# Pinduino-Nano-Sys11b.net
KiCad netlist of a schematic drawn in EAGLE
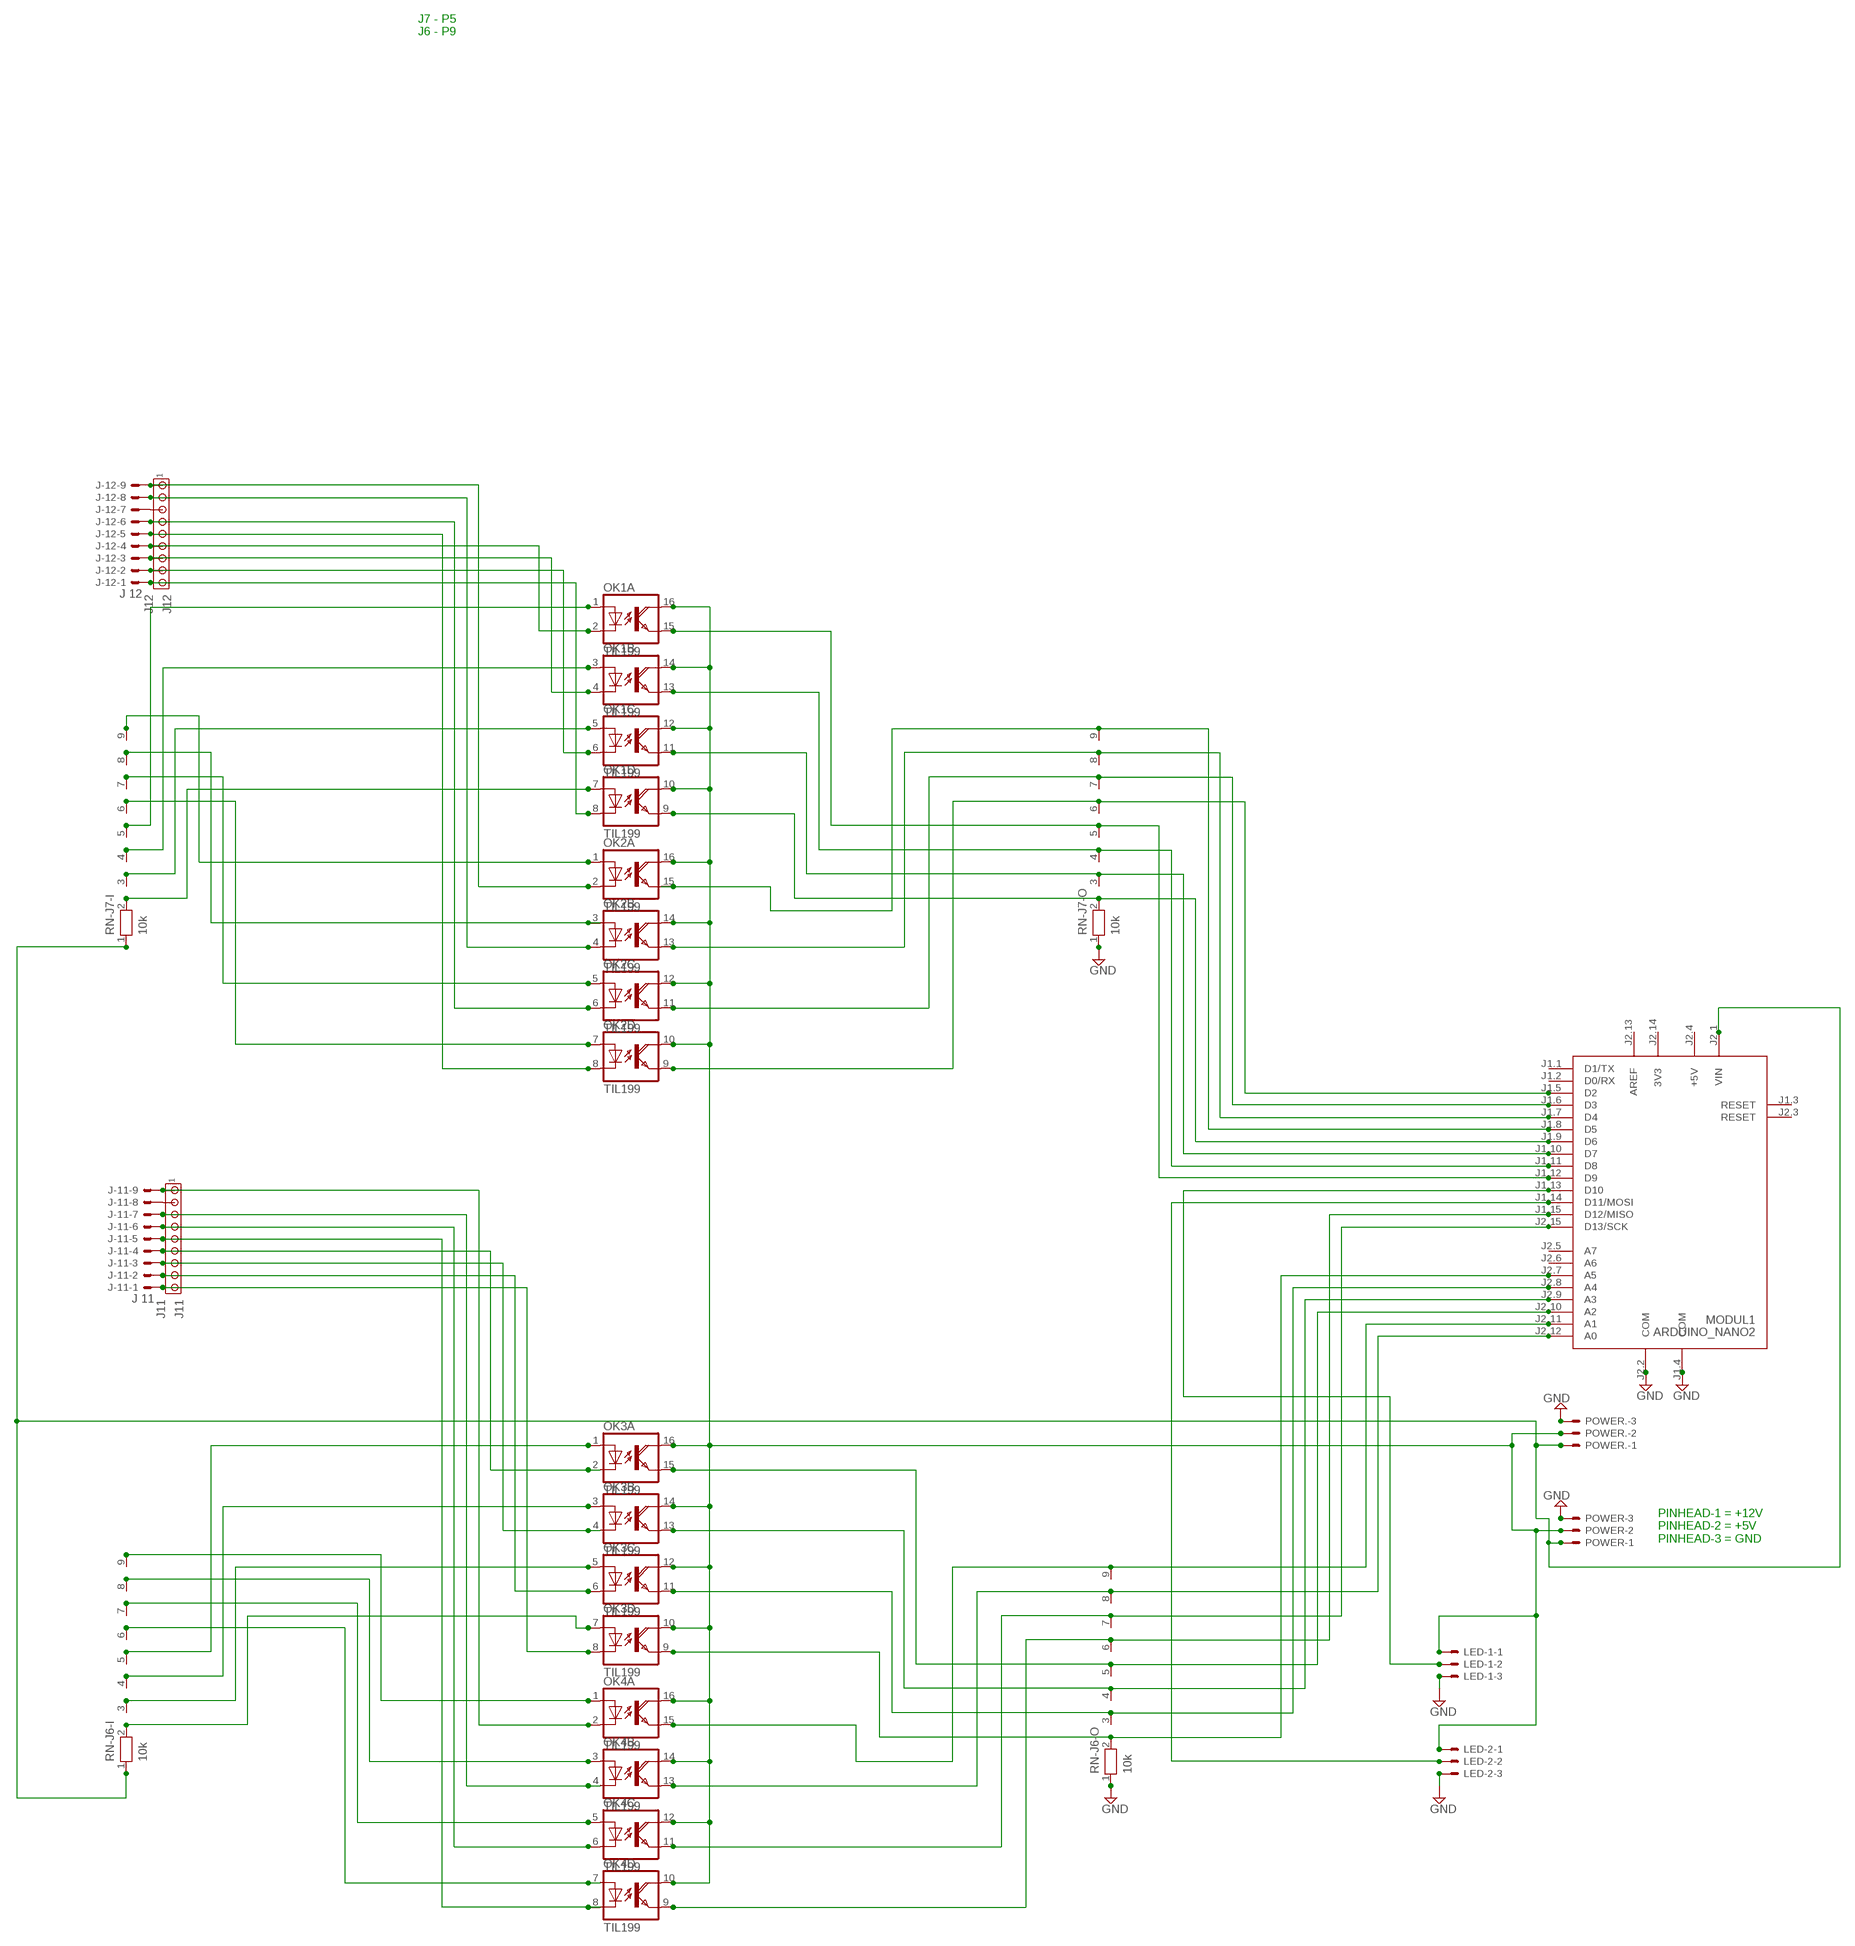
[diagram p0: schematic, sheet 1]

(export (version "E")
  (design (tool "Eeschema 10.0.6"))
  (components
    (comp (ref "J-11")
      (value "J 11")
      (footprint "eagle-import:KK-156-9")
      (libsource (lib "eagle-import") (part "KK-156-9"))
    )
    (comp (ref "J-12")
      (value "J 12")
      (footprint "eagle-import:KK-156-9")
      (libsource (lib "eagle-import") (part "KK-156-9"))
    )
    (comp (ref "J11")
      (value "J11")
      (footprint "eagle-import:1X9MTA")
      (libsource (lib "eagle-import") (part "MTA09-156"))
    )
    (comp (ref "J12")
      (value "J12")
      (footprint "eagle-import:1X9MTA")
      (libsource (lib "eagle-import") (part "MTA09-156"))
    )
    (comp (ref "LED-1")
      (value "22-23-2031")
      (footprint "eagle-import:22-23-2031")
      (fields (field (name "MF") "MOLEX"))
      (libsource (lib "eagle-import") (part "22-23-2031"))
    )
    (comp (ref "LED-2")
      (value "22-23-2031")
      (footprint "eagle-import:22-23-2031")
      (fields (field (name "MF") "MOLEX"))
      (libsource (lib "eagle-import") (part "22-23-2031"))
    )
    (comp (ref "MODUL1")
      (value "ARDUINO_NANO2")
      (footprint "eagle-import:ARDUINO_NANO2")
      (libsource (lib "eagle-import") (part "ARDUINO_NANO2"))
    )
    (comp (ref "OK1")
      (value "TIL199")
      (footprint "eagle-import:DIL16")
      (fields (field (name "MPN") "TIL 199"))
      (libsource (lib "eagle-import") (part "TIL199"))
    )
    (comp (ref "OK2")
      (value "TIL199")
      (footprint "eagle-import:DIL16")
      (fields (field (name "MPN") "TIL 199"))
      (libsource (lib "eagle-import") (part "TIL199"))
    )
    (comp (ref "OK3")
      (value "TIL199")
      (footprint "eagle-import:DIL16")
      (fields (field (name "MPN") "TIL 199"))
      (libsource (lib "eagle-import") (part "TIL199"))
    )
    (comp (ref "OK4")
      (value "TIL199")
      (footprint "eagle-import:DIL16")
      (fields (field (name "MPN") "TIL 199"))
      (libsource (lib "eagle-import") (part "TIL199"))
    )
    (comp (ref "POWER")
      (value "22-23-2031")
      (footprint "eagle-import:22-23-2031")
      (fields (field (name "MF") "MOLEX"))
      (libsource (lib "eagle-import") (part "22-23-2031"))
    )
    (comp (ref "POWER.")
      (value "22-23-2031")
      (footprint "eagle-import:22-23-2031")
      (fields (field (name "MF") "MOLEX"))
      (libsource (lib "eagle-import") (part "22-23-2031"))
    )
    (comp (ref "RN-J6-I")
      (value "10k")
      (footprint "eagle-import:RN-9")
      (libsource (lib "eagle-import") (part "RN08"))
    )
    (comp (ref "RN-J6-O")
      (value "10k")
      (footprint "eagle-import:RN-9")
      (libsource (lib "eagle-import") (part "RN08"))
    )
    (comp (ref "RN-J7-I")
      (value "10k")
      (footprint "eagle-import:RN-9")
      (libsource (lib "eagle-import") (part "RN08"))
    )
    (comp (ref "RN-J7-O")
      (value "10k")
      (footprint "eagle-import:RN-9")
      (libsource (lib "eagle-import") (part "RN08"))
    )
  )
  (nets
    (net (code "1") (name "/+5V") (class "Default")
      (node (ref "MODUL1") (pin "J2.4") (pinfunction "+5V_J2.4") (pintype "power_in"))
    )
    (net (code "2") (name "/3V3") (class "Default")
      (node (ref "MODUL1") (pin "J2.14") (pinfunction "3V3_J2.14") (pintype "power_in"))
    )
    (net (code "3") (name "/AREF") (class "Default")
      (node (ref "MODUL1") (pin "J2.13") (pinfunction "AREF_J2.13") (pintype "power_in"))
    )
    (net (code "4") (name "GND") (class "Default")
      (node (ref "LED-1") (pin "3") (pinfunction "S_3") (pintype "passive"))
      (node (ref "LED-2") (pin "3") (pinfunction "S_3") (pintype "passive"))
      (node (ref "MODUL1") (pin "J1.4") (pinfunction "COM_J1.4") (pintype "power_in"))
      (node (ref "MODUL1") (pin "J2.2") (pinfunction "COM_J2.2") (pintype "power_in"))
      (node (ref "POWER") (pin "3") (pinfunction "S_3") (pintype "passive"))
      (node (ref "POWER.") (pin "3") (pinfunction "S_3") (pintype "passive"))
      (node (ref "RN-J6-O") (pin "1") (pinfunction "1_1") (pintype "passive"))
      (node (ref "RN-J7-O") (pin "1") (pinfunction "1_1") (pintype "passive"))
    )
    (net (code "5") (name "Net-(J-11A-S)") (class "Default")
      (node (ref "J-11") (pin "1") (pinfunction "S_1") (pintype "passive"))
      (node (ref "J11") (pin "9") (pinfunction "9_9") (pintype "passive"))
      (node (ref "OK3") (pin "8") (pinfunction "C_8") (pintype "passive"))
    )
    (net (code "6") (name "Net-(J-11B-S)") (class "Default")
      (node (ref "J-11") (pin "2") (pinfunction "S_2") (pintype "passive"))
      (node (ref "J11") (pin "8") (pinfunction "8_8") (pintype "passive"))
      (node (ref "OK3") (pin "6") (pinfunction "C_6") (pintype "passive"))
    )
    (net (code "7") (name "Net-(J-11C-S)") (class "Default")
      (node (ref "J-11") (pin "3") (pinfunction "S_3") (pintype "passive"))
      (node (ref "J11") (pin "7") (pinfunction "7_7") (pintype "passive"))
      (node (ref "OK3") (pin "4") (pinfunction "C_4") (pintype "passive"))
    )
    (net (code "8") (name "Net-(J-11D-S)") (class "Default")
      (node (ref "J-11") (pin "4") (pinfunction "S_4") (pintype "passive"))
      (node (ref "J11") (pin "6") (pinfunction "6_6") (pintype "passive"))
      (node (ref "OK3") (pin "2") (pinfunction "C_2") (pintype "passive"))
    )
    (net (code "9") (name "Net-(J-11E-S)") (class "Default")
      (node (ref "J-11") (pin "5") (pinfunction "S_5") (pintype "passive"))
      (node (ref "J11") (pin "5") (pinfunction "5_5") (pintype "passive"))
      (node (ref "OK4") (pin "8") (pinfunction "C_8") (pintype "passive"))
    )
    (net (code "10") (name "Net-(J-11F-S)") (class "Default")
      (node (ref "J-11") (pin "6") (pinfunction "S_6") (pintype "passive"))
      (node (ref "J11") (pin "4") (pinfunction "4_4") (pintype "passive"))
      (node (ref "OK4") (pin "6") (pinfunction "C_6") (pintype "passive"))
    )
    (net (code "11") (name "Net-(J-11G-S)") (class "Default")
      (node (ref "J-11") (pin "7") (pinfunction "S_7") (pintype "passive"))
      (node (ref "J11") (pin "3") (pinfunction "3_3") (pintype "passive"))
      (node (ref "OK4") (pin "4") (pinfunction "C_4") (pintype "passive"))
    )
    (net (code "12") (name "Net-(J-11H-S)") (class "Default")
      (node (ref "J-11") (pin "8") (pinfunction "S_8") (pintype "passive"))
      (node (ref "J11") (pin "2") (pinfunction "2_2") (pintype "passive"))
    )
    (net (code "13") (name "Net-(J-11I-S)") (class "Default")
      (node (ref "J-11") (pin "9") (pinfunction "S_9") (pintype "passive"))
      (node (ref "J11") (pin "1") (pinfunction "1_1") (pintype "passive"))
      (node (ref "OK4") (pin "2") (pinfunction "C_2") (pintype "passive"))
    )
    (net (code "14") (name "Net-(J-12A-S)") (class "Default")
      (node (ref "J-12") (pin "1") (pinfunction "S_1") (pintype "passive"))
      (node (ref "J12") (pin "9") (pinfunction "9_9") (pintype "passive"))
      (node (ref "OK1") (pin "8") (pinfunction "C_8") (pintype "passive"))
    )
    (net (code "15") (name "Net-(J-12B-S)") (class "Default")
      (node (ref "J-12") (pin "2") (pinfunction "S_2") (pintype "passive"))
      (node (ref "J12") (pin "8") (pinfunction "8_8") (pintype "passive"))
      (node (ref "OK1") (pin "6") (pinfunction "C_6") (pintype "passive"))
    )
    (net (code "16") (name "Net-(J-12C-S)") (class "Default")
      (node (ref "J-12") (pin "3") (pinfunction "S_3") (pintype "passive"))
      (node (ref "J12") (pin "7") (pinfunction "7_7") (pintype "passive"))
      (node (ref "OK1") (pin "4") (pinfunction "C_4") (pintype "passive"))
    )
    (net (code "17") (name "Net-(J-12D-S)") (class "Default")
      (node (ref "J-12") (pin "4") (pinfunction "S_4") (pintype "passive"))
      (node (ref "J12") (pin "6") (pinfunction "6_6") (pintype "passive"))
      (node (ref "OK1") (pin "2") (pinfunction "C_2") (pintype "passive"))
    )
    (net (code "18") (name "Net-(J-12E-S)") (class "Default")
      (node (ref "J-12") (pin "5") (pinfunction "S_5") (pintype "passive"))
      (node (ref "J12") (pin "5") (pinfunction "5_5") (pintype "passive"))
      (node (ref "OK2") (pin "8") (pinfunction "C_8") (pintype "passive"))
    )
    (net (code "19") (name "Net-(J-12F-S)") (class "Default")
      (node (ref "J-12") (pin "6") (pinfunction "S_6") (pintype "passive"))
      (node (ref "J12") (pin "4") (pinfunction "4_4") (pintype "passive"))
      (node (ref "OK2") (pin "6") (pinfunction "C_6") (pintype "passive"))
    )
    (net (code "20") (name "Net-(J-12G-S)") (class "Default")
      (node (ref "J-12") (pin "7") (pinfunction "S_7") (pintype "passive"))
      (node (ref "J12") (pin "3") (pinfunction "3_3") (pintype "passive"))
    )
    (net (code "21") (name "Net-(J-12H-S)") (class "Default")
      (node (ref "J-12") (pin "8") (pinfunction "S_8") (pintype "passive"))
      (node (ref "J12") (pin "2") (pinfunction "2_2") (pintype "passive"))
      (node (ref "OK2") (pin "4") (pinfunction "C_4") (pintype "passive"))
    )
    (net (code "22") (name "Net-(J-12I-S)") (class "Default")
      (node (ref "J-12") (pin "9") (pinfunction "S_9") (pintype "passive"))
      (node (ref "J12") (pin "1") (pinfunction "1_1") (pintype "passive"))
      (node (ref "OK2") (pin "2") (pinfunction "C_2") (pintype "passive"))
    )
    (net (code "23") (name "Net-(LED-1A-S)") (class "Default")
      (node (ref "LED-1") (pin "1") (pinfunction "S_1") (pintype "passive"))
      (node (ref "LED-2") (pin "1") (pinfunction "S_1") (pintype "passive"))
      (node (ref "OK1") (pin "10") (pinfunction "COL_10") (pintype "passive"))
      (node (ref "OK1") (pin "12") (pinfunction "COL_12") (pintype "passive"))
      (node (ref "OK1") (pin "14") (pinfunction "COL_14") (pintype "passive"))
      (node (ref "OK1") (pin "16") (pinfunction "COL_16") (pintype "passive"))
      (node (ref "OK2") (pin "10") (pinfunction "COL_10") (pintype "passive"))
      (node (ref "OK2") (pin "12") (pinfunction "COL_12") (pintype "passive"))
      (node (ref "OK2") (pin "14") (pinfunction "COL_14") (pintype "passive"))
      (node (ref "OK2") (pin "16") (pinfunction "COL_16") (pintype "passive"))
      (node (ref "OK3") (pin "10") (pinfunction "COL_10") (pintype "passive"))
      (node (ref "OK3") (pin "12") (pinfunction "COL_12") (pintype "passive"))
      (node (ref "OK3") (pin "14") (pinfunction "COL_14") (pintype "passive"))
      (node (ref "OK3") (pin "16") (pinfunction "COL_16") (pintype "passive"))
      (node (ref "OK4") (pin "10") (pinfunction "COL_10") (pintype "passive"))
      (node (ref "OK4") (pin "12") (pinfunction "COL_12") (pintype "passive"))
      (node (ref "OK4") (pin "14") (pinfunction "COL_14") (pintype "passive"))
      (node (ref "OK4") (pin "16") (pinfunction "COL_16") (pintype "passive"))
      (node (ref "POWER") (pin "2") (pinfunction "S_2") (pintype "passive"))
      (node (ref "POWER.") (pin "2") (pinfunction "S_2") (pintype "passive"))
    )
    (net (code "24") (name "Net-(LED-1B-S)") (class "Default")
      (node (ref "LED-1") (pin "2") (pinfunction "S_2") (pintype "passive"))
      (node (ref "MODUL1") (pin "J1.13") (pinfunction "D10_J1.13") (pintype "bidirectional"))
    )
    (net (code "25") (name "Net-(LED-2B-S)") (class "Default")
      (node (ref "LED-2") (pin "2") (pinfunction "S_2") (pintype "passive"))
      (node (ref "MODUL1") (pin "J1.14") (pinfunction "D11/MOSI_J1.14") (pintype "bidirectional"))
    )
    (net (code "26") (name "Net-(MODUL1-A0)") (class "Default")
      (node (ref "MODUL1") (pin "J2.12") (pinfunction "A0_J2.12") (pintype "bidirectional"))
      (node (ref "OK4") (pin "13") (pinfunction "EMI_13") (pintype "passive"))
      (node (ref "RN-J6-O") (pin "8") (pinfunction "8_8") (pintype "passive"))
    )
    (net (code "27") (name "Net-(MODUL1-A1)") (class "Default")
      (node (ref "MODUL1") (pin "J2.11") (pinfunction "A1_J2.11") (pintype "bidirectional"))
      (node (ref "OK4") (pin "15") (pinfunction "EMI_15") (pintype "passive"))
      (node (ref "RN-J6-O") (pin "9") (pinfunction "9_9") (pintype "passive"))
    )
    (net (code "28") (name "Net-(MODUL1-A2)") (class "Default")
      (node (ref "MODUL1") (pin "J2.10") (pinfunction "A2_J2.10") (pintype "bidirectional"))
      (node (ref "OK3") (pin "15") (pinfunction "EMI_15") (pintype "passive"))
      (node (ref "RN-J6-O") (pin "5") (pinfunction "5_5") (pintype "passive"))
    )
    (net (code "29") (name "Net-(MODUL1-A3)") (class "Default")
      (node (ref "MODUL1") (pin "J2.9") (pinfunction "A3_J2.9") (pintype "bidirectional"))
      (node (ref "OK3") (pin "13") (pinfunction "EMI_13") (pintype "passive"))
      (node (ref "RN-J6-O") (pin "4") (pinfunction "4_4") (pintype "passive"))
    )
    (net (code "30") (name "Net-(MODUL1-A4)") (class "Default")
      (node (ref "MODUL1") (pin "J2.8") (pinfunction "A4_J2.8") (pintype "bidirectional"))
      (node (ref "OK3") (pin "11") (pinfunction "EMI_11") (pintype "passive"))
      (node (ref "RN-J6-O") (pin "3") (pinfunction "3_3") (pintype "passive"))
    )
    (net (code "31") (name "Net-(MODUL1-A5)") (class "Default")
      (node (ref "MODUL1") (pin "J2.7") (pinfunction "A5_J2.7") (pintype "bidirectional"))
      (node (ref "OK3") (pin "9") (pinfunction "EMI_9") (pintype "passive"))
      (node (ref "RN-J6-O") (pin "2") (pinfunction "2_2") (pintype "passive"))
    )
    (net (code "32") (name "Net-(MODUL1-D2)") (class "Default")
      (node (ref "MODUL1") (pin "J1.5") (pinfunction "D2_J1.5") (pintype "bidirectional"))
      (node (ref "OK2") (pin "9") (pinfunction "EMI_9") (pintype "passive"))
      (node (ref "RN-J7-O") (pin "6") (pinfunction "6_6") (pintype "passive"))
    )
    (net (code "33") (name "Net-(MODUL1-D3)") (class "Default")
      (node (ref "MODUL1") (pin "J1.6") (pinfunction "D3_J1.6") (pintype "bidirectional"))
      (node (ref "OK2") (pin "11") (pinfunction "EMI_11") (pintype "passive"))
      (node (ref "RN-J7-O") (pin "7") (pinfunction "7_7") (pintype "passive"))
    )
    (net (code "34") (name "Net-(MODUL1-D4)") (class "Default")
      (node (ref "MODUL1") (pin "J1.7") (pinfunction "D4_J1.7") (pintype "bidirectional"))
      (node (ref "OK2") (pin "13") (pinfunction "EMI_13") (pintype "passive"))
      (node (ref "RN-J7-O") (pin "8") (pinfunction "8_8") (pintype "passive"))
    )
    (net (code "35") (name "Net-(MODUL1-D5)") (class "Default")
      (node (ref "MODUL1") (pin "J1.8") (pinfunction "D5_J1.8") (pintype "bidirectional"))
      (node (ref "OK2") (pin "15") (pinfunction "EMI_15") (pintype "passive"))
      (node (ref "RN-J7-O") (pin "9") (pinfunction "9_9") (pintype "passive"))
    )
    (net (code "36") (name "Net-(MODUL1-D6)") (class "Default")
      (node (ref "MODUL1") (pin "J1.9") (pinfunction "D6_J1.9") (pintype "bidirectional"))
      (node (ref "OK1") (pin "9") (pinfunction "EMI_9") (pintype "passive"))
      (node (ref "RN-J7-O") (pin "2") (pinfunction "2_2") (pintype "passive"))
    )
    (net (code "37") (name "Net-(MODUL1-D7)") (class "Default")
      (node (ref "MODUL1") (pin "J1.10") (pinfunction "D7_J1.10") (pintype "bidirectional"))
      (node (ref "OK1") (pin "11") (pinfunction "EMI_11") (pintype "passive"))
      (node (ref "RN-J7-O") (pin "3") (pinfunction "3_3") (pintype "passive"))
    )
    (net (code "38") (name "Net-(MODUL1-D8)") (class "Default")
      (node (ref "MODUL1") (pin "J1.11") (pinfunction "D8_J1.11") (pintype "bidirectional"))
      (node (ref "OK1") (pin "13") (pinfunction "EMI_13") (pintype "passive"))
      (node (ref "RN-J7-O") (pin "4") (pinfunction "4_4") (pintype "passive"))
    )
    (net (code "39") (name "Net-(MODUL1-D9)") (class "Default")
      (node (ref "MODUL1") (pin "J1.12") (pinfunction "D9_J1.12") (pintype "bidirectional"))
      (node (ref "OK1") (pin "15") (pinfunction "EMI_15") (pintype "passive"))
      (node (ref "RN-J7-O") (pin "5") (pinfunction "5_5") (pintype "passive"))
    )
    (net (code "40") (name "Net-(MODUL1-D12{slash}MISO)") (class "Default")
      (node (ref "MODUL1") (pin "J1.15") (pinfunction "D12/MISO_J1.15") (pintype "bidirectional"))
      (node (ref "OK4") (pin "9") (pinfunction "EMI_9") (pintype "passive"))
      (node (ref "RN-J6-O") (pin "6") (pinfunction "6_6") (pintype "passive"))
    )
    (net (code "41") (name "Net-(MODUL1-D13{slash}SCK)") (class "Default")
      (node (ref "MODUL1") (pin "J2.15") (pinfunction "D13/SCK_J2.15") (pintype "bidirectional"))
      (node (ref "OK4") (pin "11") (pinfunction "EMI_11") (pintype "passive"))
      (node (ref "RN-J6-O") (pin "7") (pinfunction "7_7") (pintype "passive"))
    )
    (net (code "42") (name "Net-(MODUL1-VIN)") (class "Default")
      (node (ref "MODUL1") (pin "J2.1") (pinfunction "VIN_J2.1") (pintype "power_in"))
      (node (ref "POWER") (pin "1") (pinfunction "S_1") (pintype "passive"))
      (node (ref "POWER.") (pin "1") (pinfunction "S_1") (pintype "passive"))
      (node (ref "RN-J6-I") (pin "1") (pinfunction "1_1") (pintype "passive"))
      (node (ref "RN-J7-I") (pin "1") (pinfunction "1_1") (pintype "passive"))
    )
    (net (code "43") (name "Net-(OK1A-A)") (class "Default")
      (node (ref "OK1") (pin "1") (pinfunction "A_1") (pintype "passive"))
      (node (ref "RN-J7-I") (pin "5") (pinfunction "5_5") (pintype "passive"))
    )
    (net (code "44") (name "Net-(OK1B-A)") (class "Default")
      (node (ref "OK1") (pin "3") (pinfunction "A_3") (pintype "passive"))
      (node (ref "RN-J7-I") (pin "4") (pinfunction "4_4") (pintype "passive"))
    )
    (net (code "45") (name "Net-(OK1C-A)") (class "Default")
      (node (ref "OK1") (pin "5") (pinfunction "A_5") (pintype "passive"))
      (node (ref "RN-J7-I") (pin "3") (pinfunction "3_3") (pintype "passive"))
    )
    (net (code "46") (name "Net-(OK1D-A)") (class "Default")
      (node (ref "OK1") (pin "7") (pinfunction "A_7") (pintype "passive"))
      (node (ref "RN-J7-I") (pin "2") (pinfunction "2_2") (pintype "passive"))
    )
    (net (code "47") (name "Net-(OK2A-A)") (class "Default")
      (node (ref "OK2") (pin "1") (pinfunction "A_1") (pintype "passive"))
      (node (ref "RN-J7-I") (pin "9") (pinfunction "9_9") (pintype "passive"))
    )
    (net (code "48") (name "Net-(OK2B-A)") (class "Default")
      (node (ref "OK2") (pin "3") (pinfunction "A_3") (pintype "passive"))
      (node (ref "RN-J7-I") (pin "8") (pinfunction "8_8") (pintype "passive"))
    )
    (net (code "49") (name "Net-(OK2C-A)") (class "Default")
      (node (ref "OK2") (pin "5") (pinfunction "A_5") (pintype "passive"))
      (node (ref "RN-J7-I") (pin "7") (pinfunction "7_7") (pintype "passive"))
    )
    (net (code "50") (name "Net-(OK2D-A)") (class "Default")
      (node (ref "OK2") (pin "7") (pinfunction "A_7") (pintype "passive"))
      (node (ref "RN-J7-I") (pin "6") (pinfunction "6_6") (pintype "passive"))
    )
    (net (code "51") (name "Net-(OK3A-A)") (class "Default")
      (node (ref "OK3") (pin "1") (pinfunction "A_1") (pintype "passive"))
      (node (ref "RN-J6-I") (pin "5") (pinfunction "5_5") (pintype "passive"))
    )
    (net (code "52") (name "Net-(OK3B-A)") (class "Default")
      (node (ref "OK3") (pin "3") (pinfunction "A_3") (pintype "passive"))
      (node (ref "RN-J6-I") (pin "4") (pinfunction "4_4") (pintype "passive"))
    )
    (net (code "53") (name "Net-(OK3C-A)") (class "Default")
      (node (ref "OK3") (pin "5") (pinfunction "A_5") (pintype "passive"))
      (node (ref "RN-J6-I") (pin "3") (pinfunction "3_3") (pintype "passive"))
    )
    (net (code "54") (name "Net-(OK3D-A)") (class "Default")
      (node (ref "OK3") (pin "7") (pinfunction "A_7") (pintype "passive"))
      (node (ref "RN-J6-I") (pin "2") (pinfunction "2_2") (pintype "passive"))
    )
    (net (code "55") (name "Net-(OK4A-A)") (class "Default")
      (node (ref "OK4") (pin "1") (pinfunction "A_1") (pintype "passive"))
      (node (ref "RN-J6-I") (pin "9") (pinfunction "9_9") (pintype "passive"))
    )
    (net (code "56") (name "Net-(OK4B-A)") (class "Default")
      (node (ref "OK4") (pin "3") (pinfunction "A_3") (pintype "passive"))
      (node (ref "RN-J6-I") (pin "8") (pinfunction "8_8") (pintype "passive"))
    )
    (net (code "57") (name "Net-(OK4C-A)") (class "Default")
      (node (ref "OK4") (pin "5") (pinfunction "A_5") (pintype "passive"))
      (node (ref "RN-J6-I") (pin "7") (pinfunction "7_7") (pintype "passive"))
    )
    (net (code "58") (name "Net-(OK4D-A)") (class "Default")
      (node (ref "OK4") (pin "7") (pinfunction "A_7") (pintype "passive"))
      (node (ref "RN-J6-I") (pin "6") (pinfunction "6_6") (pintype "passive"))
    )
    (net (code "59") (name "unconnected-(MODUL1-A6-PadJ2.6)") (class "Default")
      (node (ref "MODUL1") (pin "J2.6") (pinfunction "A6_J2.6") (pintype "bidirectional"))
    )
    (net (code "60") (name "unconnected-(MODUL1-A7-PadJ2.5)") (class "Default")
      (node (ref "MODUL1") (pin "J2.5") (pinfunction "A7_J2.5") (pintype "bidirectional"))
    )
    (net (code "61") (name "unconnected-(MODUL1-D0{slash}RX-PadJ1.2)") (class "Default")
      (node (ref "MODUL1") (pin "J1.2") (pinfunction "D0/RX_J1.2") (pintype "bidirectional"))
    )
    (net (code "62") (name "unconnected-(MODUL1-D1{slash}TX-PadJ1.1)") (class "Default")
      (node (ref "MODUL1") (pin "J1.1") (pinfunction "D1/TX_J1.1") (pintype "bidirectional"))
    )
    (net (code "63") (name "unconnected-(MODUL1-RESET-PadJ1.3)") (class "Default")
      (node (ref "MODUL1") (pin "J1.3") (pinfunction "RESET_J1.3") (pintype "bidirectional"))
    )
    (net (code "64") (name "unconnected-(MODUL1-RESET-PadJ2.3)") (class "Default")
      (node (ref "MODUL1") (pin "J2.3") (pinfunction "RESET_J2.3") (pintype "bidirectional"))
    )
  )
)
